# Programmer.net
KiCad netlist of a schematic drawn in EAGLE
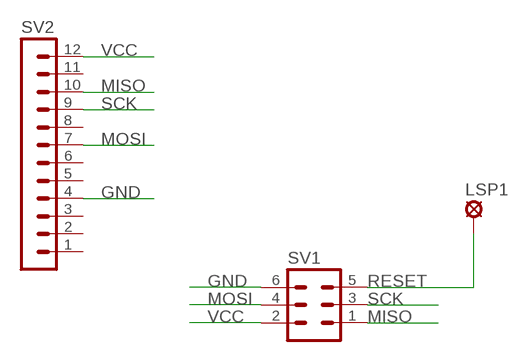
[diagram p0: schematic, sheet 1]

(export (version "E")
  (design (tool "Eeschema 10.0.6"))
  (components
    (comp (ref "LSP1")
      (value "MCS10B")
      (footprint "eagle-import:MCS10B")
      (libsource (lib "eagle-import") (part "MCS10B"))
    )
    (comp (ref "SV1")
      (value "MA03-2")
      (footprint "eagle-import:MA03-2")
      (libsource (lib "eagle-import") (part "MA03-2"))
    )
    (comp (ref "SV2")
      (value "MA12-1W")
      (footprint "eagle-import:MA12-1W")
      (libsource (lib "eagle-import") (part "MA12-1W"))
    )
  )
  (nets
    (net (code "1") (name "/GND") (class "Default")
      (node (ref "SV1") (pin "6") (pinfunction "6_6") (pintype "passive"))
      (node (ref "SV2") (pin "4") (pinfunction "4_4") (pintype "passive"))
    )
    (net (code "2") (name "/MISO") (class "Default")
      (node (ref "SV1") (pin "1") (pinfunction "1_1") (pintype "passive"))
      (node (ref "SV2") (pin "10") (pinfunction "10_10") (pintype "passive"))
    )
    (net (code "3") (name "/MOSI") (class "Default")
      (node (ref "SV1") (pin "4") (pinfunction "4_4") (pintype "passive"))
      (node (ref "SV2") (pin "7") (pinfunction "7_7") (pintype "passive"))
    )
    (net (code "4") (name "/RESET") (class "Default")
      (node (ref "LSP1") (pin "MP") (pinfunction "MP_MP") (pintype "passive"))
      (node (ref "SV1") (pin "5") (pinfunction "5_5") (pintype "passive"))
    )
    (net (code "5") (name "/SCK") (class "Default")
      (node (ref "SV1") (pin "3") (pinfunction "3_3") (pintype "passive"))
      (node (ref "SV2") (pin "9") (pinfunction "9_9") (pintype "passive"))
    )
    (net (code "6") (name "/VCC") (class "Default")
      (node (ref "SV1") (pin "2") (pinfunction "2_2") (pintype "passive"))
      (node (ref "SV2") (pin "12") (pinfunction "12_12") (pintype "passive"))
    )
    (net (code "7") (name "unconnected-(SV2-Pad1)") (class "Default")
      (node (ref "SV2") (pin "1") (pinfunction "1_1") (pintype "passive"))
    )
    (net (code "8") (name "unconnected-(SV2-Pad2)") (class "Default")
      (node (ref "SV2") (pin "2") (pinfunction "2_2") (pintype "passive"))
    )
    (net (code "9") (name "unconnected-(SV2-Pad3)") (class "Default")
      (node (ref "SV2") (pin "3") (pinfunction "3_3") (pintype "passive"))
    )
    (net (code "10") (name "unconnected-(SV2-Pad5)") (class "Default")
      (node (ref "SV2") (pin "5") (pinfunction "5_5") (pintype "passive"))
    )
    (net (code "11") (name "unconnected-(SV2-Pad6)") (class "Default")
      (node (ref "SV2") (pin "6") (pinfunction "6_6") (pintype "passive"))
    )
    (net (code "12") (name "unconnected-(SV2-Pad8)") (class "Default")
      (node (ref "SV2") (pin "8") (pinfunction "8_8") (pintype "passive"))
    )
    (net (code "13") (name "unconnected-(SV2-Pad11)") (class "Default")
      (node (ref "SV2") (pin "11") (pinfunction "11_11") (pintype "passive"))
    )
  )
)
